# Motor_driver_sheet.net
KiCad netlist of a schematic drawn in Altium Designer
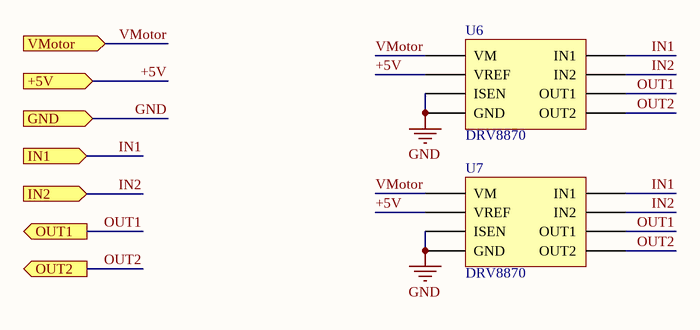
[diagram p0: Motor driver sheet.SchDoc]

(export (version "E")
  (design (tool "Eeschema 10.0.6"))
  (components
    (comp (ref "U6")
      (value "DRV8870")
      (footprint "8-Pin HSOP")
      (libsource (lib "AlexChistiakov") (part "DRV8870"))
    )
    (comp (ref "U7")
      (value "DRV8870")
      (footprint "8-Pin HSOP")
      (libsource (lib "AlexChistiakov") (part "DRV8870"))
    )
  )
  (nets
    (net (code "1") (name "/+5V") (class "Default")
      (node (ref "U6") (pin "4") (pinfunction "VREF_4") (pintype "passive"))
      (node (ref "U7") (pin "4") (pinfunction "VREF_4") (pintype "passive"))
    )
    (net (code "2") (name "/IN1") (class "Default")
      (node (ref "U6") (pin "2") (pinfunction "IN1_2") (pintype "passive"))
      (node (ref "U7") (pin "2") (pinfunction "IN1_2") (pintype "passive"))
    )
    (net (code "3") (name "/IN2") (class "Default")
      (node (ref "U6") (pin "3") (pinfunction "IN2_3") (pintype "passive"))
      (node (ref "U7") (pin "3") (pinfunction "IN2_3") (pintype "passive"))
    )
    (net (code "4") (name "/OUT1") (class "Default")
      (node (ref "U6") (pin "6") (pinfunction "OUT1_6") (pintype "passive"))
      (node (ref "U7") (pin "6") (pinfunction "OUT1_6") (pintype "passive"))
    )
    (net (code "5") (name "/OUT2") (class "Default")
      (node (ref "U6") (pin "8") (pinfunction "OUT2_8") (pintype "passive"))
      (node (ref "U7") (pin "8") (pinfunction "OUT2_8") (pintype "passive"))
    )
    (net (code "6") (name "/VMotor") (class "Default")
      (node (ref "U6") (pin "5") (pinfunction "VM_5") (pintype "passive"))
      (node (ref "U7") (pin "5") (pinfunction "VM_5") (pintype "passive"))
    )
    (net (code "7") (name "GND") (class "Default")
      (node (ref "U6") (pin "1") (pinfunction "GND_1") (pintype "passive"))
      (node (ref "U6") (pin "7") (pinfunction "ISEN_7") (pintype "passive"))
      (node (ref "U7") (pin "1") (pinfunction "GND_1") (pintype "passive"))
      (node (ref "U7") (pin "7") (pinfunction "ISEN_7") (pintype "passive"))
    )
  )
)
